# IDS_ADC_SMT_v2.net
KiCad netlist of a schematic drawn in EAGLE
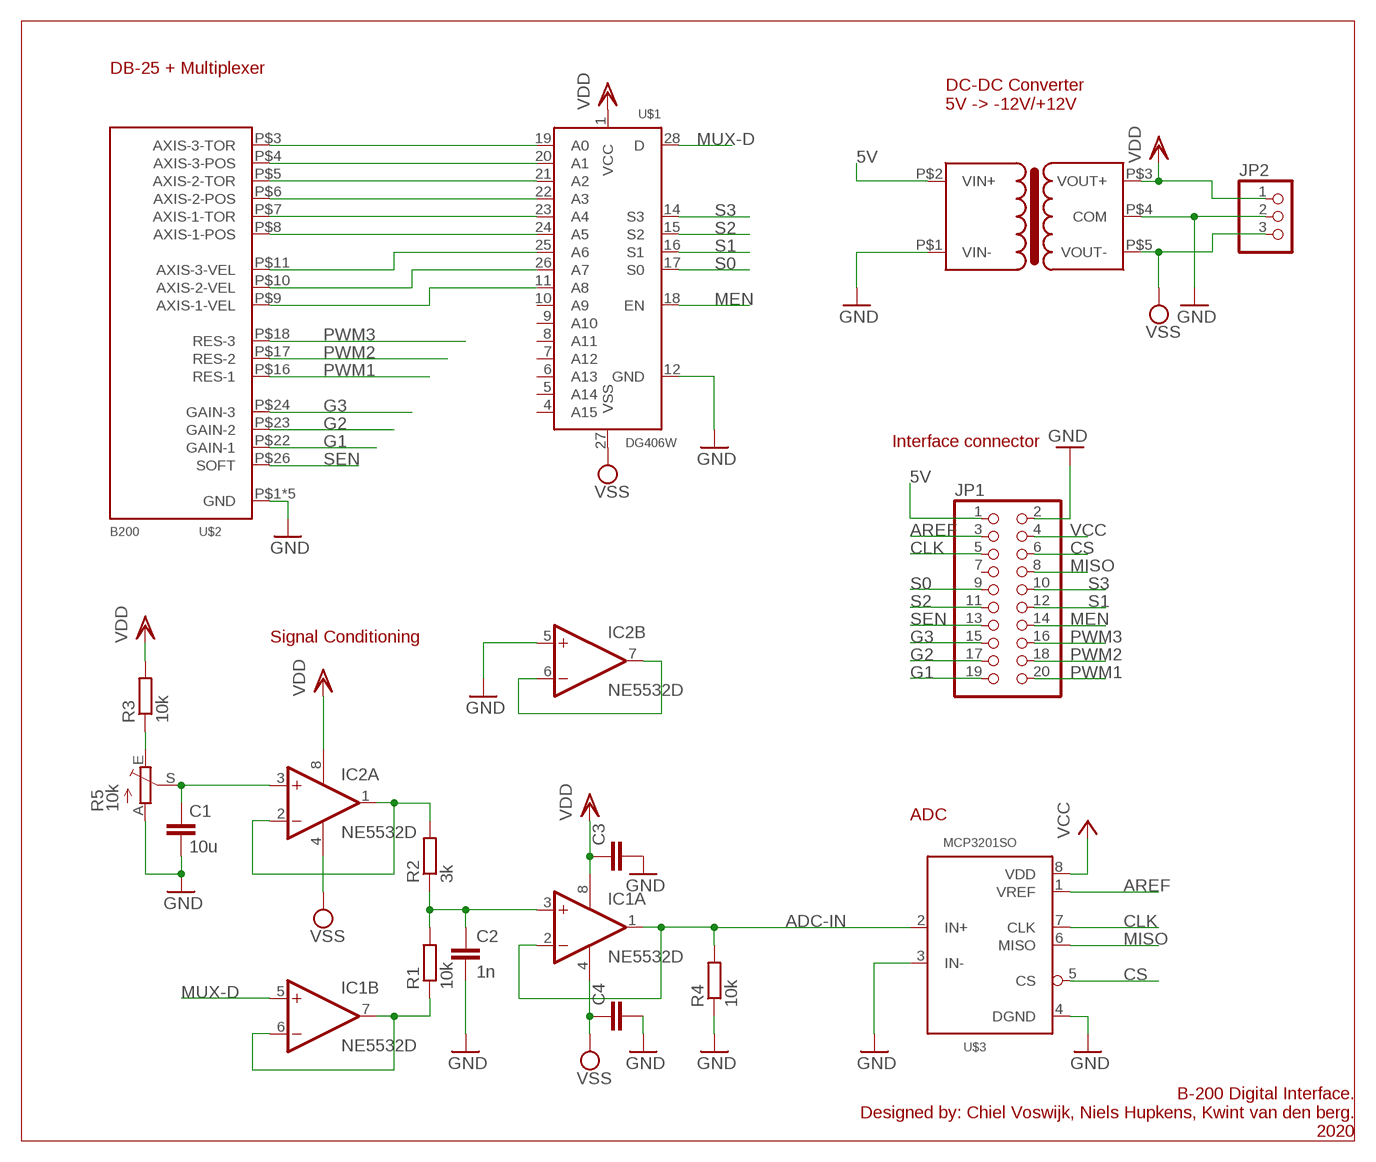
[diagram p0: schematic, sheet 1]

(export (version "E")
  (design (tool "Eeschema 10.0.6"))
  (components
    (comp (ref "C1")
      (value "10u")
      (footprint "eagle-import:C1210")
      (libsource (lib "eagle-import") (part "C-EUC1210"))
    )
    (comp (ref "C2")
      (value "1n")
      (footprint "eagle-import:C0805")
      (libsource (lib "eagle-import") (part "C-EUC0805"))
    )
    (comp (ref "C3")
      (value "C-EUC0805")
      (footprint "eagle-import:C0805")
      (libsource (lib "eagle-import") (part "C-EUC0805"))
    )
    (comp (ref "C4")
      (value "C-EUC0805")
      (footprint "eagle-import:C0805")
      (libsource (lib "eagle-import") (part "C-EUC0805"))
    )
    (comp (ref "IC1")
      (value "NE5532D")
      (footprint "eagle-import:SO08")
      (libsource (lib "eagle-import") (part "NE5532D"))
    )
    (comp (ref "IC2")
      (value "NE5532D")
      (footprint "eagle-import:SO08")
      (libsource (lib "eagle-import") (part "NE5532D"))
    )
    (comp (ref "JP1")
      (value "PINHD-2X10")
      (footprint "eagle-import:2X10")
      (libsource (lib "eagle-import") (part "PINHD-2X10"))
    )
    (comp (ref "JP2")
      (value "PINHD-1X3")
      (footprint "eagle-import:1X03")
      (libsource (lib "eagle-import") (part "PINHD-1X3"))
    )
    (comp (ref "R1")
      (value "10k")
      (footprint "eagle-import:R0805")
      (libsource (lib "eagle-import") (part "R-EU_R0805"))
    )
    (comp (ref "R2")
      (value "3k")
      (footprint "eagle-import:R0805")
      (libsource (lib "eagle-import") (part "R-EU_R0805"))
    )
    (comp (ref "R3")
      (value "10k")
      (footprint "eagle-import:R0805")
      (libsource (lib "eagle-import") (part "R-EU_R0805"))
    )
    (comp (ref "R4")
      (value "10k")
      (footprint "eagle-import:R0805")
      (libsource (lib "eagle-import") (part "R-EU_R0805"))
    )
    (comp (ref "R5")
      (value "10k")
      (footprint "eagle-import:RJ9W")
      (libsource (lib "eagle-import") (part "TRIM_EU-RJ9W"))
    )
    (comp (ref "U$1")
      (value "DG406W")
      (footprint "eagle-import:SO-28W")
      (libsource (lib "eagle-import") (part "DG406W"))
    )
    (comp (ref "U$2")
      (value "B200")
      (footprint "eagle-import:PARALLEL")
      (libsource (lib "eagle-import") (part "B200"))
    )
    (comp (ref "U$3")
      (value "MCP3201SO")
      (footprint "eagle-import:SO-8")
      (libsource (lib "eagle-import") (part "MCP3201SO"))
    )
    (comp (ref "U$4")
      (value "TRACO-DR-NE")
      (footprint "eagle-import:TRACO-DCDC-SIP6")
      (libsource (lib "eagle-import") (part "TRACO-DR-NE"))
    )
  )
  (nets
    (net (code "1") (name "/5V") (class "Default")
      (node (ref "JP1") (pin "1") (pinfunction "1_1") (pintype "passive"))
      (node (ref "U$4") (pin "P$2") (pinfunction "VIN+_P$2") (pintype "bidirectional"))
    )
    (net (code "2") (name "/ADC-IN") (class "Default")
      (node (ref "IC1") (pin "1") (pinfunction "OUT_1") (pintype "output"))
      (node (ref "IC1") (pin "2") (pinfunction "-IN_2") (pintype "input"))
      (node (ref "R4") (pin "2") (pinfunction "2_2") (pintype "passive"))
      (node (ref "U$3") (pin "2") (pinfunction "IN+_2") (pintype "input"))
    )
    (net (code "3") (name "/AREF") (class "Default")
      (node (ref "JP1") (pin "3") (pinfunction "3_3") (pintype "passive"))
      (node (ref "U$3") (pin "1") (pinfunction "VREF_1") (pintype "bidirectional"))
    )
    (net (code "4") (name "/CLK") (class "Default")
      (node (ref "JP1") (pin "5") (pinfunction "5_5") (pintype "passive"))
      (node (ref "U$3") (pin "7") (pinfunction "CLK_7") (pintype "bidirectional"))
    )
    (net (code "5") (name "/CS") (class "Default")
      (node (ref "JP1") (pin "6") (pinfunction "6_6") (pintype "passive"))
      (node (ref "U$3") (pin "5") (pinfunction "CS_5") (pintype "bidirectional"))
    )
    (net (code "6") (name "/G1") (class "Default")
      (node (ref "JP1") (pin "19") (pinfunction "19_19") (pintype "passive"))
      (node (ref "U$2") (pin "P$22") (pinfunction "GAIN-1_P$22") (pintype "output"))
    )
    (net (code "7") (name "/G2") (class "Default")
      (node (ref "JP1") (pin "17") (pinfunction "17_17") (pintype "passive"))
      (node (ref "U$2") (pin "P$23") (pinfunction "GAIN-2_P$23") (pintype "output"))
    )
    (net (code "8") (name "/G3") (class "Default")
      (node (ref "JP1") (pin "15") (pinfunction "15_15") (pintype "passive"))
      (node (ref "U$2") (pin "P$24") (pinfunction "GAIN-3_P$24") (pintype "output"))
    )
    (net (code "9") (name "/MEN") (class "Default")
      (node (ref "JP1") (pin "14") (pinfunction "14_14") (pintype "passive"))
      (node (ref "U$1") (pin "18") (pinfunction "EN_18") (pintype "input"))
    )
    (net (code "10") (name "/MISO") (class "Default")
      (node (ref "JP1") (pin "8") (pinfunction "8_8") (pintype "passive"))
      (node (ref "U$3") (pin "6") (pinfunction "MISO_6") (pintype "bidirectional"))
    )
    (net (code "11") (name "/MUX-D") (class "Default")
      (node (ref "IC1") (pin "5") (pinfunction "+IN_5") (pintype "input"))
      (node (ref "U$1") (pin "28") (pinfunction "D_28") (pintype "bidirectional"))
    )
    (net (code "12") (name "/PWM1") (class "Default")
      (node (ref "JP1") (pin "20") (pinfunction "20_20") (pintype "passive"))
      (node (ref "U$2") (pin "P$16") (pinfunction "RES-1_P$16") (pintype "output"))
    )
    (net (code "13") (name "/PWM2") (class "Default")
      (node (ref "JP1") (pin "18") (pinfunction "18_18") (pintype "passive"))
      (node (ref "U$2") (pin "P$17") (pinfunction "RES-2_P$17") (pintype "output"))
    )
    (net (code "14") (name "/PWM3") (class "Default")
      (node (ref "JP1") (pin "16") (pinfunction "16_16") (pintype "passive"))
      (node (ref "U$2") (pin "P$18") (pinfunction "RES-3_P$18") (pintype "output"))
    )
    (net (code "15") (name "/S0") (class "Default")
      (node (ref "JP1") (pin "9") (pinfunction "9_9") (pintype "passive"))
      (node (ref "U$1") (pin "17") (pinfunction "S0_17") (pintype "input"))
    )
    (net (code "16") (name "/S1") (class "Default")
      (node (ref "JP1") (pin "12") (pinfunction "12_12") (pintype "passive"))
      (node (ref "U$1") (pin "16") (pinfunction "S1_16") (pintype "input"))
    )
    (net (code "17") (name "/S2") (class "Default")
      (node (ref "JP1") (pin "11") (pinfunction "11_11") (pintype "passive"))
      (node (ref "U$1") (pin "15") (pinfunction "S2_15") (pintype "input"))
    )
    (net (code "18") (name "/S3") (class "Default")
      (node (ref "JP1") (pin "10") (pinfunction "10_10") (pintype "passive"))
      (node (ref "U$1") (pin "14") (pinfunction "S3_14") (pintype "input"))
    )
    (net (code "19") (name "/SEN") (class "Default")
      (node (ref "JP1") (pin "13") (pinfunction "13_13") (pintype "passive"))
      (node (ref "U$2") (pin "P$26") (pinfunction "SOFT_P$26") (pintype "output"))
    )
    (net (code "20") (name "GND") (class "Default")
      (node (ref "C1") (pin "2") (pinfunction "2_2") (pintype "passive"))
      (node (ref "C2") (pin "2") (pinfunction "2_2") (pintype "passive"))
      (node (ref "C3") (pin "2") (pinfunction "2_2") (pintype "passive"))
      (node (ref "C4") (pin "2") (pinfunction "2_2") (pintype "passive"))
      (node (ref "IC2") (pin "5") (pinfunction "+IN_5") (pintype "input"))
      (node (ref "JP1") (pin "2") (pinfunction "2_2") (pintype "passive"))
      (node (ref "JP2") (pin "2") (pinfunction "2_2") (pintype "passive"))
      (node (ref "R4") (pin "1") (pinfunction "1_1") (pintype "passive"))
      (node (ref "R5") (pin "A") (pinfunction "A_A") (pintype "passive"))
      (node (ref "U$1") (pin "12") (pinfunction "GND_12") (pintype "open_collector"))
      (node (ref "U$2") (pin "P$1") (pinfunction "GND_P$1") (pintype "output"))
      (node (ref "U$2") (pin "P$19") (pinfunction "GND_P$19") (pintype "output"))
      (node (ref "U$2") (pin "P$2") (pinfunction "GND_P$2") (pintype "output"))
      (node (ref "U$2") (pin "P$20") (pinfunction "GND_P$20") (pintype "output"))
      (node (ref "U$2") (pin "P$21") (pinfunction "GND_P$21") (pintype "output"))
      (node (ref "U$3") (pin "3") (pinfunction "IN-_3") (pintype "input"))
      (node (ref "U$3") (pin "4") (pinfunction "DGND_4") (pintype "power_in"))
      (node (ref "U$4") (pin "P$1") (pinfunction "VIN-_P$1") (pintype "bidirectional"))
      (node (ref "U$4") (pin "P$4") (pinfunction "COM_P$4") (pintype "bidirectional"))
    )
    (net (code "21") (name "Net-(IC1A-+IN)") (class "Default")
      (node (ref "C2") (pin "1") (pinfunction "1_1") (pintype "passive"))
      (node (ref "IC1") (pin "3") (pinfunction "+IN_3") (pintype "input"))
      (node (ref "R1") (pin "2") (pinfunction "2_2") (pintype "passive"))
      (node (ref "R2") (pin "1") (pinfunction "1_1") (pintype "passive"))
    )
    (net (code "22") (name "Net-(IC1B--IN)") (class "Default")
      (node (ref "IC1") (pin "6") (pinfunction "-IN_6") (pintype "input"))
      (node (ref "IC1") (pin "7") (pinfunction "OUT_7") (pintype "output"))
      (node (ref "R1") (pin "1") (pinfunction "1_1") (pintype "passive"))
    )
    (net (code "23") (name "Net-(IC2A-+IN)") (class "Default")
      (node (ref "C1") (pin "1") (pinfunction "1_1") (pintype "passive"))
      (node (ref "IC2") (pin "3") (pinfunction "+IN_3") (pintype "input"))
      (node (ref "R5") (pin "S") (pinfunction "S_S") (pintype "passive"))
    )
    (net (code "24") (name "Net-(IC2A--IN)") (class "Default")
      (node (ref "IC2") (pin "1") (pinfunction "OUT_1") (pintype "output"))
      (node (ref "IC2") (pin "2") (pinfunction "-IN_2") (pintype "input"))
      (node (ref "R2") (pin "2") (pinfunction "2_2") (pintype "passive"))
    )
    (net (code "25") (name "Net-(IC2B--IN)") (class "Default")
      (node (ref "IC2") (pin "6") (pinfunction "-IN_6") (pintype "input"))
      (node (ref "IC2") (pin "7") (pinfunction "OUT_7") (pintype "output"))
    )
    (net (code "26") (name "Net-(R3-Pad1)") (class "Default")
      (node (ref "R3") (pin "1") (pinfunction "1_1") (pintype "passive"))
      (node (ref "R5") (pin "E") (pinfunction "E_E") (pintype "passive"))
    )
    (net (code "27") (name "Net-(U$1-A0)") (class "Default")
      (node (ref "U$1") (pin "19") (pinfunction "A0_19") (pintype "bidirectional"))
      (node (ref "U$2") (pin "P$3") (pinfunction "AXIS-3-TOR_P$3") (pintype "output"))
    )
    (net (code "28") (name "Net-(U$1-A1)") (class "Default")
      (node (ref "U$1") (pin "20") (pinfunction "A1_20") (pintype "bidirectional"))
      (node (ref "U$2") (pin "P$4") (pinfunction "AXIS-3-POS_P$4") (pintype "output"))
    )
    (net (code "29") (name "Net-(U$1-A2)") (class "Default")
      (node (ref "U$1") (pin "21") (pinfunction "A2_21") (pintype "bidirectional"))
      (node (ref "U$2") (pin "P$5") (pinfunction "AXIS-2-TOR_P$5") (pintype "output"))
    )
    (net (code "30") (name "Net-(U$1-A3)") (class "Default")
      (node (ref "U$1") (pin "22") (pinfunction "A3_22") (pintype "bidirectional"))
      (node (ref "U$2") (pin "P$6") (pinfunction "AXIS-2-POS_P$6") (pintype "output"))
    )
    (net (code "31") (name "Net-(U$1-A4)") (class "Default")
      (node (ref "U$1") (pin "23") (pinfunction "A4_23") (pintype "bidirectional"))
      (node (ref "U$2") (pin "P$7") (pinfunction "AXIS-1-TOR_P$7") (pintype "output"))
    )
    (net (code "32") (name "Net-(U$1-A5)") (class "Default")
      (node (ref "U$1") (pin "24") (pinfunction "A5_24") (pintype "bidirectional"))
      (node (ref "U$2") (pin "P$8") (pinfunction "AXIS-1-POS_P$8") (pintype "output"))
    )
    (net (code "33") (name "Net-(U$1-A6)") (class "Default")
      (node (ref "U$1") (pin "25") (pinfunction "A6_25") (pintype "bidirectional"))
      (node (ref "U$2") (pin "P$11") (pinfunction "AXIS-3-VEL_P$11") (pintype "output"))
    )
    (net (code "34") (name "Net-(U$1-A7)") (class "Default")
      (node (ref "U$1") (pin "26") (pinfunction "A7_26") (pintype "bidirectional"))
      (node (ref "U$2") (pin "P$10") (pinfunction "AXIS-2-VEL_P$10") (pintype "output"))
    )
    (net (code "35") (name "Net-(U$1-A8)") (class "Default")
      (node (ref "U$1") (pin "11") (pinfunction "A8_11") (pintype "bidirectional"))
      (node (ref "U$2") (pin "P$9") (pinfunction "AXIS-1-VEL_P$9") (pintype "output"))
    )
    (net (code "36") (name "VCC") (class "Default")
      (node (ref "JP1") (pin "4") (pinfunction "4_4") (pintype "passive"))
      (node (ref "U$3") (pin "8") (pinfunction "VDD_8") (pintype "power_in"))
    )
    (net (code "37") (name "VDD") (class "Default")
      (node (ref "C3") (pin "1") (pinfunction "1_1") (pintype "passive"))
      (node (ref "IC1") (pin "8") (pinfunction "V+_8") (pintype "power_in"))
      (node (ref "IC2") (pin "8") (pinfunction "V+_8") (pintype "power_in"))
      (node (ref "JP2") (pin "1") (pinfunction "1_1") (pintype "passive"))
      (node (ref "R3") (pin "2") (pinfunction "2_2") (pintype "passive"))
      (node (ref "U$1") (pin "1") (pinfunction "VCC_1") (pintype "power_in"))
      (node (ref "U$4") (pin "P$3") (pinfunction "VOUT+_P$3") (pintype "bidirectional"))
    )
    (net (code "38") (name "VSS") (class "Default")
      (node (ref "C4") (pin "1") (pinfunction "1_1") (pintype "passive"))
      (node (ref "IC1") (pin "4") (pinfunction "V-_4") (pintype "power_in"))
      (node (ref "IC2") (pin "4") (pinfunction "V-_4") (pintype "power_in"))
      (node (ref "JP2") (pin "3") (pinfunction "3_3") (pintype "passive"))
      (node (ref "U$1") (pin "27") (pinfunction "VSS_27") (pintype "open_collector"))
      (node (ref "U$4") (pin "P$5") (pinfunction "VOUT-_P$5") (pintype "bidirectional"))
    )
    (net (code "39") (name "unconnected-(JP1-Pad7)") (class "Default")
      (node (ref "JP1") (pin "7") (pinfunction "7_7") (pintype "passive"))
    )
    (net (code "40") (name "unconnected-(U$1-A9-Pad10)") (class "Default")
      (node (ref "U$1") (pin "10") (pinfunction "A9_10") (pintype "bidirectional"))
    )
    (net (code "41") (name "unconnected-(U$1-A10-Pad9)") (class "Default")
      (node (ref "U$1") (pin "9") (pinfunction "A10_9") (pintype "bidirectional"))
    )
    (net (code "42") (name "unconnected-(U$1-A11-Pad8)") (class "Default")
      (node (ref "U$1") (pin "8") (pinfunction "A11_8") (pintype "bidirectional"))
    )
    (net (code "43") (name "unconnected-(U$1-A12-Pad7)") (class "Default")
      (node (ref "U$1") (pin "7") (pinfunction "A12_7") (pintype "bidirectional"))
    )
    (net (code "44") (name "unconnected-(U$1-A13-Pad6)") (class "Default")
      (node (ref "U$1") (pin "6") (pinfunction "A13_6") (pintype "bidirectional"))
    )
    (net (code "45") (name "unconnected-(U$1-A14-Pad5)") (class "Default")
      (node (ref "U$1") (pin "5") (pinfunction "A14_5") (pintype "bidirectional"))
    )
    (net (code "46") (name "unconnected-(U$1-A15-Pad4)") (class "Default")
      (node (ref "U$1") (pin "4") (pinfunction "A15_4") (pintype "bidirectional"))
    )
  )
)
